# TRICORDER.net
KiCad netlist of a schematic drawn in EAGLE
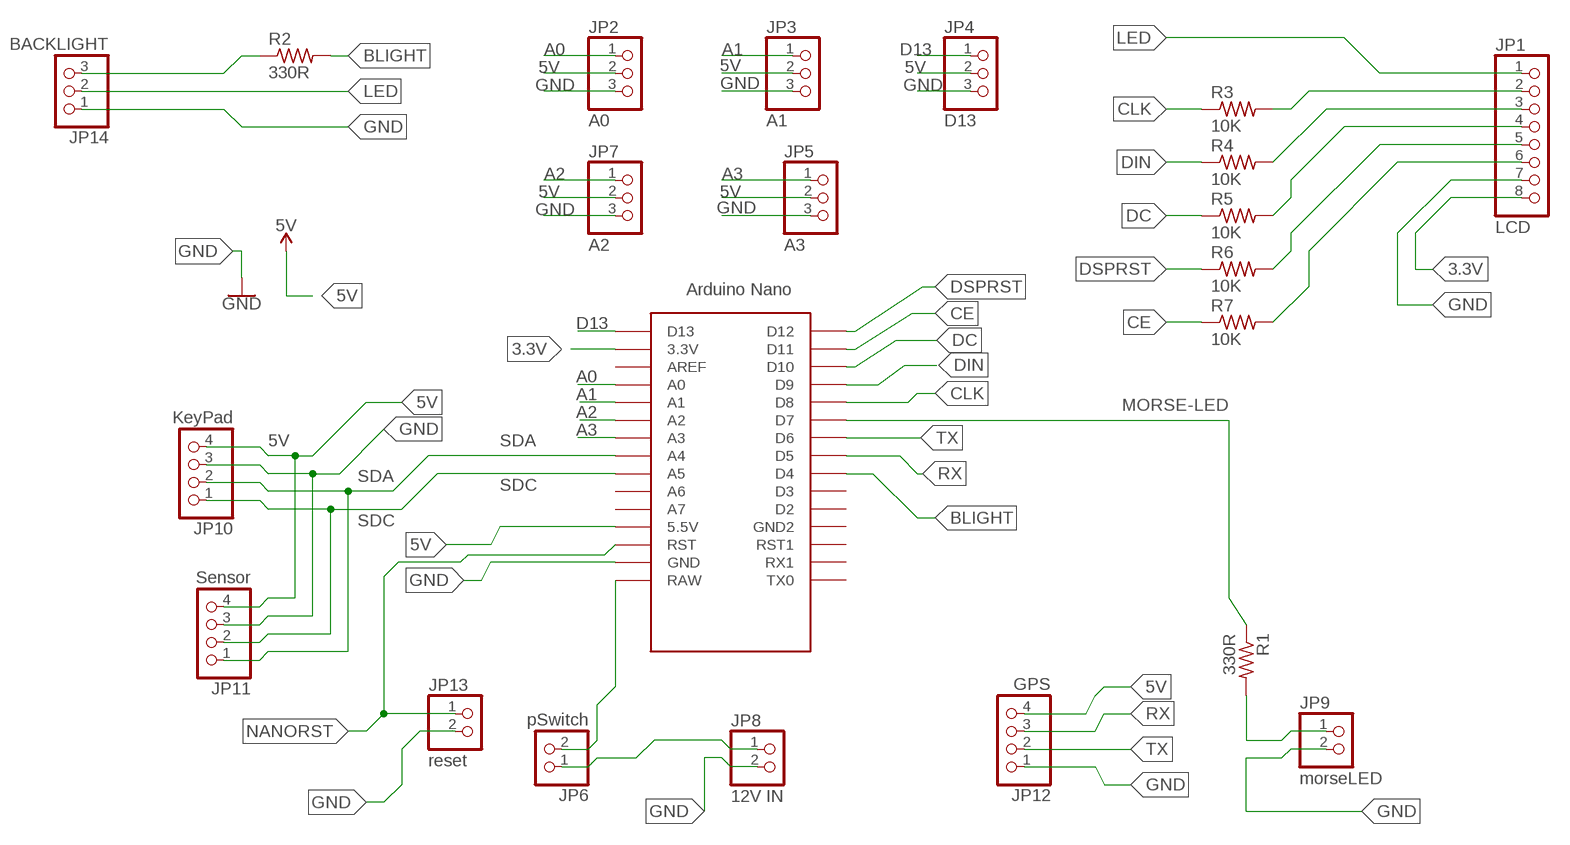
[diagram p0: schematic, sheet 1]

(export (version "E")
  (design (tool "Eeschema 10.0.6"))
  (components
    (comp (ref "JP1")
      (value "LCD")
      (footprint "eagle-import:1X08_90")
      (libsource (lib "eagle-import") (part "PINHD-1X8/90"))
    )
    (comp (ref "JP2")
      (value "A0")
      (footprint "eagle-import:1X03")
      (libsource (lib "eagle-import") (part "PINHD-1X3"))
    )
    (comp (ref "JP3")
      (value "A1")
      (footprint "eagle-import:1X03")
      (libsource (lib "eagle-import") (part "PINHD-1X3"))
    )
    (comp (ref "JP4")
      (value "D13")
      (footprint "eagle-import:1X03")
      (libsource (lib "eagle-import") (part "PINHD-1X3"))
    )
    (comp (ref "JP5")
      (value "A3")
      (footprint "eagle-import:1X03")
      (libsource (lib "eagle-import") (part "PINHD-1X3"))
    )
    (comp (ref "JP6")
      (value "pSwitch")
      (footprint "eagle-import:1X02_90")
      (libsource (lib "eagle-import") (part "PINHD-1X2/90"))
    )
    (comp (ref "JP7")
      (value "A2")
      (footprint "eagle-import:1X03")
      (libsource (lib "eagle-import") (part "PINHD-1X3"))
    )
    (comp (ref "JP8")
      (value "12V IN")
      (footprint "eagle-import:1X02_90")
      (libsource (lib "eagle-import") (part "PINHD-1X2/90"))
    )
    (comp (ref "JP9")
      (value "morseLED")
      (footprint "eagle-import:1X02_90")
      (libsource (lib "eagle-import") (part "PINHD-1X2/90"))
    )
    (comp (ref "JP10")
      (value "KeyPad")
      (footprint "eagle-import:1X04_90")
      (libsource (lib "eagle-import") (part "PINHD-1X4/90"))
    )
    (comp (ref "JP11")
      (value "Sensor")
      (footprint "eagle-import:1X04_90")
      (libsource (lib "eagle-import") (part "PINHD-1X4/90"))
    )
    (comp (ref "JP12")
      (value "GPS")
      (footprint "eagle-import:1X04_90")
      (libsource (lib "eagle-import") (part "PINHD-1X4/90"))
    )
    (comp (ref "JP13")
      (value "reset")
      (footprint "eagle-import:1X02_90")
      (libsource (lib "eagle-import") (part "PINHD-1X2/90"))
    )
    (comp (ref "JP14")
      (value "BACKLIGHT")
      (footprint "eagle-import:1X03_90")
      (libsource (lib "eagle-import") (part "PINHD-1X3/90"))
    )
    (comp (ref "R1")
      (value "330R")
      (footprint "eagle-import:0207_9")
      (libsource (lib "eagle-import") (part "R-US_0207/9"))
    )
    (comp (ref "R2")
      (value "330R")
      (footprint "eagle-import:0207_9")
      (libsource (lib "eagle-import") (part "R-US_0207/9"))
    )
    (comp (ref "R3")
      (value "10K")
      (footprint "eagle-import:0207_9")
      (libsource (lib "eagle-import") (part "R-US_0207/9"))
    )
    (comp (ref "R4")
      (value "10K")
      (footprint "eagle-import:0207_9")
      (libsource (lib "eagle-import") (part "R-US_0207/9"))
    )
    (comp (ref "R5")
      (value "10K")
      (footprint "eagle-import:0207_9")
      (libsource (lib "eagle-import") (part "R-US_0207/9"))
    )
    (comp (ref "R6")
      (value "10K")
      (footprint "eagle-import:0207_9")
      (libsource (lib "eagle-import") (part "R-US_0207/9"))
    )
    (comp (ref "R7")
      (value "10K")
      (footprint "eagle-import:0207_9")
      (libsource (lib "eagle-import") (part "R-US_0207/9"))
    )
    (comp (ref "U$1")
      (value "NANO")
      (footprint "eagle-import:NANO")
      (libsource (lib "eagle-import") (part "NANO"))
    )
  )
  (nets
    (net (code "1") (name "/A0") (class "Default")
      (node (ref "JP2") (pin "1") (pinfunction "1_1") (pintype "passive"))
      (node (ref "U$1") (pin "A0") (pinfunction "A0_A0") (pintype "bidirectional"))
    )
    (net (code "2") (name "/A1") (class "Default")
      (node (ref "JP3") (pin "1") (pinfunction "1_1") (pintype "passive"))
      (node (ref "U$1") (pin "A1") (pinfunction "A1_A1") (pintype "bidirectional"))
    )
    (net (code "3") (name "/A2") (class "Default")
      (node (ref "JP7") (pin "1") (pinfunction "1_1") (pintype "passive"))
      (node (ref "U$1") (pin "A2") (pinfunction "A2_A2") (pintype "bidirectional"))
    )
    (net (code "4") (name "/A3") (class "Default")
      (node (ref "JP5") (pin "1") (pinfunction "1_1") (pintype "passive"))
      (node (ref "U$1") (pin "A3") (pinfunction "A3_A3") (pintype "bidirectional"))
    )
    (net (code "5") (name "/D13") (class "Default")
      (node (ref "JP4") (pin "1") (pinfunction "1_1") (pintype "passive"))
      (node (ref "U$1") (pin "D13") (pinfunction "D13_D13") (pintype "bidirectional"))
    )
    (net (code "6") (name "/MORSE-LED") (class "Default")
      (node (ref "R1") (pin "1") (pinfunction "1_1") (pintype "passive"))
      (node (ref "U$1") (pin "D7") (pinfunction "D7_D7") (pintype "bidirectional"))
    )
    (net (code "7") (name "/SDA") (class "Default")
      (node (ref "JP10") (pin "2") (pinfunction "2_2") (pintype "passive"))
      (node (ref "JP11") (pin "1") (pinfunction "1_1") (pintype "passive"))
      (node (ref "U$1") (pin "A4") (pinfunction "A4_A4") (pintype "bidirectional"))
    )
    (net (code "8") (name "/SDC") (class "Default")
      (node (ref "JP10") (pin "1") (pinfunction "1_1") (pintype "passive"))
      (node (ref "JP11") (pin "2") (pinfunction "2_2") (pintype "passive"))
      (node (ref "U$1") (pin "A5") (pinfunction "A5_A5") (pintype "bidirectional"))
    )
    (net (code "9") (name "3.3V") (class "Default")
      (node (ref "JP1") (pin "8") (pinfunction "8_8") (pintype "passive"))
      (node (ref "U$1") (pin "3.3V") (pinfunction "3.3V_3.3V") (pintype "bidirectional"))
    )
    (net (code "10") (name "5V") (class "Default")
      (node (ref "JP10") (pin "4") (pinfunction "4_4") (pintype "passive"))
      (node (ref "JP11") (pin "4") (pinfunction "4_4") (pintype "passive"))
      (node (ref "JP12") (pin "4") (pinfunction "4_4") (pintype "passive"))
      (node (ref "JP2") (pin "2") (pinfunction "2_2") (pintype "passive"))
      (node (ref "JP3") (pin "2") (pinfunction "2_2") (pintype "passive"))
      (node (ref "JP4") (pin "2") (pinfunction "2_2") (pintype "passive"))
      (node (ref "JP5") (pin "2") (pinfunction "2_2") (pintype "passive"))
      (node (ref "JP7") (pin "2") (pinfunction "2_2") (pintype "passive"))
      (node (ref "U$1") (pin "5V") (pinfunction "5.5V_5V") (pintype "bidirectional"))
    )
    (net (code "11") (name "BLIGHT") (class "Default")
      (node (ref "R2") (pin "2") (pinfunction "2_2") (pintype "passive"))
      (node (ref "U$1") (pin "D4") (pinfunction "D4_D4") (pintype "bidirectional"))
    )
    (net (code "12") (name "CE") (class "Default")
      (node (ref "R7") (pin "1") (pinfunction "1_1") (pintype "passive"))
      (node (ref "U$1") (pin "D11") (pinfunction "D11_D11") (pintype "bidirectional"))
    )
    (net (code "13") (name "CLK") (class "Default")
      (node (ref "R3") (pin "1") (pinfunction "1_1") (pintype "passive"))
      (node (ref "U$1") (pin "D8") (pinfunction "D8_D8") (pintype "bidirectional"))
    )
    (net (code "14") (name "DC") (class "Default")
      (node (ref "R5") (pin "1") (pinfunction "1_1") (pintype "passive"))
      (node (ref "U$1") (pin "D10") (pinfunction "D10_D10") (pintype "bidirectional"))
    )
    (net (code "15") (name "DIN") (class "Default")
      (node (ref "R4") (pin "1") (pinfunction "1_1") (pintype "passive"))
      (node (ref "U$1") (pin "D9") (pinfunction "D9_D9") (pintype "bidirectional"))
    )
    (net (code "16") (name "DSPRST") (class "Default")
      (node (ref "R6") (pin "1") (pinfunction "1_1") (pintype "passive"))
      (node (ref "U$1") (pin "D12") (pinfunction "D12_D12") (pintype "bidirectional"))
    )
    (net (code "17") (name "GND") (class "Default")
      (node (ref "JP1") (pin "7") (pinfunction "7_7") (pintype "passive"))
      (node (ref "JP10") (pin "3") (pinfunction "3_3") (pintype "passive"))
      (node (ref "JP11") (pin "3") (pinfunction "3_3") (pintype "passive"))
      (node (ref "JP12") (pin "1") (pinfunction "1_1") (pintype "passive"))
      (node (ref "JP13") (pin "2") (pinfunction "2_2") (pintype "passive"))
      (node (ref "JP14") (pin "1") (pinfunction "1_1") (pintype "passive"))
      (node (ref "JP2") (pin "3") (pinfunction "3_3") (pintype "passive"))
      (node (ref "JP3") (pin "3") (pinfunction "3_3") (pintype "passive"))
      (node (ref "JP4") (pin "3") (pinfunction "3_3") (pintype "passive"))
      (node (ref "JP5") (pin "3") (pinfunction "3_3") (pintype "passive"))
      (node (ref "JP7") (pin "3") (pinfunction "3_3") (pintype "passive"))
      (node (ref "JP8") (pin "2") (pinfunction "2_2") (pintype "passive"))
      (node (ref "JP9") (pin "2") (pinfunction "2_2") (pintype "passive"))
      (node (ref "U$1") (pin "GND") (pinfunction "GND_GND") (pintype "bidirectional"))
    )
    (net (code "18") (name "LED") (class "Default")
      (node (ref "JP1") (pin "1") (pinfunction "1_1") (pintype "passive"))
      (node (ref "JP14") (pin "2") (pinfunction "2_2") (pintype "passive"))
    )
    (net (code "19") (name "NANORST") (class "Default")
      (node (ref "JP13") (pin "1") (pinfunction "1_1") (pintype "passive"))
      (node (ref "U$1") (pin "RST") (pinfunction "RST_RST") (pintype "bidirectional"))
    )
    (net (code "20") (name "Net-(JP1-Pad2)") (class "Default")
      (node (ref "JP1") (pin "2") (pinfunction "2_2") (pintype "passive"))
      (node (ref "R3") (pin "2") (pinfunction "2_2") (pintype "passive"))
    )
    (net (code "21") (name "Net-(JP1-Pad3)") (class "Default")
      (node (ref "JP1") (pin "3") (pinfunction "3_3") (pintype "passive"))
      (node (ref "R4") (pin "2") (pinfunction "2_2") (pintype "passive"))
    )
    (net (code "22") (name "Net-(JP1-Pad4)") (class "Default")
      (node (ref "JP1") (pin "4") (pinfunction "4_4") (pintype "passive"))
      (node (ref "R5") (pin "2") (pinfunction "2_2") (pintype "passive"))
    )
    (net (code "23") (name "Net-(JP1-Pad5)") (class "Default")
      (node (ref "JP1") (pin "5") (pinfunction "5_5") (pintype "passive"))
      (node (ref "R6") (pin "2") (pinfunction "2_2") (pintype "passive"))
    )
    (net (code "24") (name "Net-(JP1-Pad6)") (class "Default")
      (node (ref "JP1") (pin "6") (pinfunction "6_6") (pintype "passive"))
      (node (ref "R7") (pin "2") (pinfunction "2_2") (pintype "passive"))
    )
    (net (code "25") (name "Net-(JP6-Pad1)") (class "Default")
      (node (ref "JP6") (pin "1") (pinfunction "1_1") (pintype "passive"))
      (node (ref "JP8") (pin "1") (pinfunction "1_1") (pintype "passive"))
    )
    (net (code "26") (name "Net-(JP6-Pad2)") (class "Default")
      (node (ref "JP6") (pin "2") (pinfunction "2_2") (pintype "passive"))
      (node (ref "U$1") (pin "RAW") (pinfunction "RAW_RAW") (pintype "bidirectional"))
    )
    (net (code "27") (name "Net-(JP9-Pad1)") (class "Default")
      (node (ref "JP9") (pin "1") (pinfunction "1_1") (pintype "passive"))
      (node (ref "R1") (pin "2") (pinfunction "2_2") (pintype "passive"))
    )
    (net (code "28") (name "Net-(JP14-Pad3)") (class "Default")
      (node (ref "JP14") (pin "3") (pinfunction "3_3") (pintype "passive"))
      (node (ref "R2") (pin "1") (pinfunction "1_1") (pintype "passive"))
    )
    (net (code "29") (name "RX") (class "Default")
      (node (ref "JP12") (pin "3") (pinfunction "3_3") (pintype "passive"))
      (node (ref "U$1") (pin "D5") (pinfunction "D5_D5") (pintype "bidirectional"))
    )
    (net (code "30") (name "TX") (class "Default")
      (node (ref "JP12") (pin "2") (pinfunction "2_2") (pintype "passive"))
      (node (ref "U$1") (pin "D6") (pinfunction "D6_D6") (pintype "bidirectional"))
    )
    (net (code "31") (name "unconnected-(U$1-GND2-PadGND1)") (class "Default")
      (node (ref "U$1") (pin "GND1") (pinfunction "GND2_GND1") (pintype "bidirectional"))
    )
    (net (code "32") (name "unconnected-(U$1-PadA6)") (class "Default")
      (node (ref "U$1") (pin "A6") (pinfunction "A6_A6") (pintype "bidirectional"))
    )
    (net (code "33") (name "unconnected-(U$1-PadA7)") (class "Default")
      (node (ref "U$1") (pin "A7") (pinfunction "A7_A7") (pintype "bidirectional"))
    )
    (net (code "34") (name "unconnected-(U$1-PadAREF)") (class "Default")
      (node (ref "U$1") (pin "AREF") (pinfunction "AREF_AREF") (pintype "bidirectional"))
    )
    (net (code "35") (name "unconnected-(U$1-PadD2)") (class "Default")
      (node (ref "U$1") (pin "D2") (pinfunction "D2_D2") (pintype "bidirectional"))
    )
    (net (code "36") (name "unconnected-(U$1-PadD3)") (class "Default")
      (node (ref "U$1") (pin "D3") (pinfunction "D3_D3") (pintype "bidirectional"))
    )
    (net (code "37") (name "unconnected-(U$1-PadICSP1)") (class "Default")
      (node (ref "U$1") (pin "ICSP1") (pinfunction "ICSP1_ICSP1") (pintype "bidirectional"))
    )
    (net (code "38") (name "unconnected-(U$1-PadICSP2)") (class "Default")
      (node (ref "U$1") (pin "ICSP2") (pinfunction "ICSP2_ICSP2") (pintype "bidirectional"))
    )
    (net (code "39") (name "unconnected-(U$1-PadICSP3)") (class "Default")
      (node (ref "U$1") (pin "ICSP3") (pinfunction "ICSP3_ICSP3") (pintype "bidirectional"))
    )
    (net (code "40") (name "unconnected-(U$1-PadICSP4)") (class "Default")
      (node (ref "U$1") (pin "ICSP4") (pinfunction "ICSP4_ICSP4") (pintype "bidirectional"))
    )
    (net (code "41") (name "unconnected-(U$1-PadICSP5)") (class "Default")
      (node (ref "U$1") (pin "ICSP5") (pinfunction "ICSP5_ICSP5") (pintype "bidirectional"))
    )
    (net (code "42") (name "unconnected-(U$1-PadICSP6)") (class "Default")
      (node (ref "U$1") (pin "ICSP6") (pinfunction "ICSP6_ICSP6") (pintype "bidirectional"))
    )
    (net (code "43") (name "unconnected-(U$1-PadRST1)") (class "Default")
      (node (ref "U$1") (pin "RST1") (pinfunction "RST1_RST1") (pintype "bidirectional"))
    )
    (net (code "44") (name "unconnected-(U$1-PadRX1)") (class "Default")
      (node (ref "U$1") (pin "RX1") (pinfunction "RX1_RX1") (pintype "bidirectional"))
    )
    (net (code "45") (name "unconnected-(U$1-PadTX0)") (class "Default")
      (node (ref "U$1") (pin "TX0") (pinfunction "TX0_TX0") (pintype "bidirectional"))
    )
  )
)
